# 3-5_TDR.net
KiCad netlist of a schematic drawn in Altium Designer
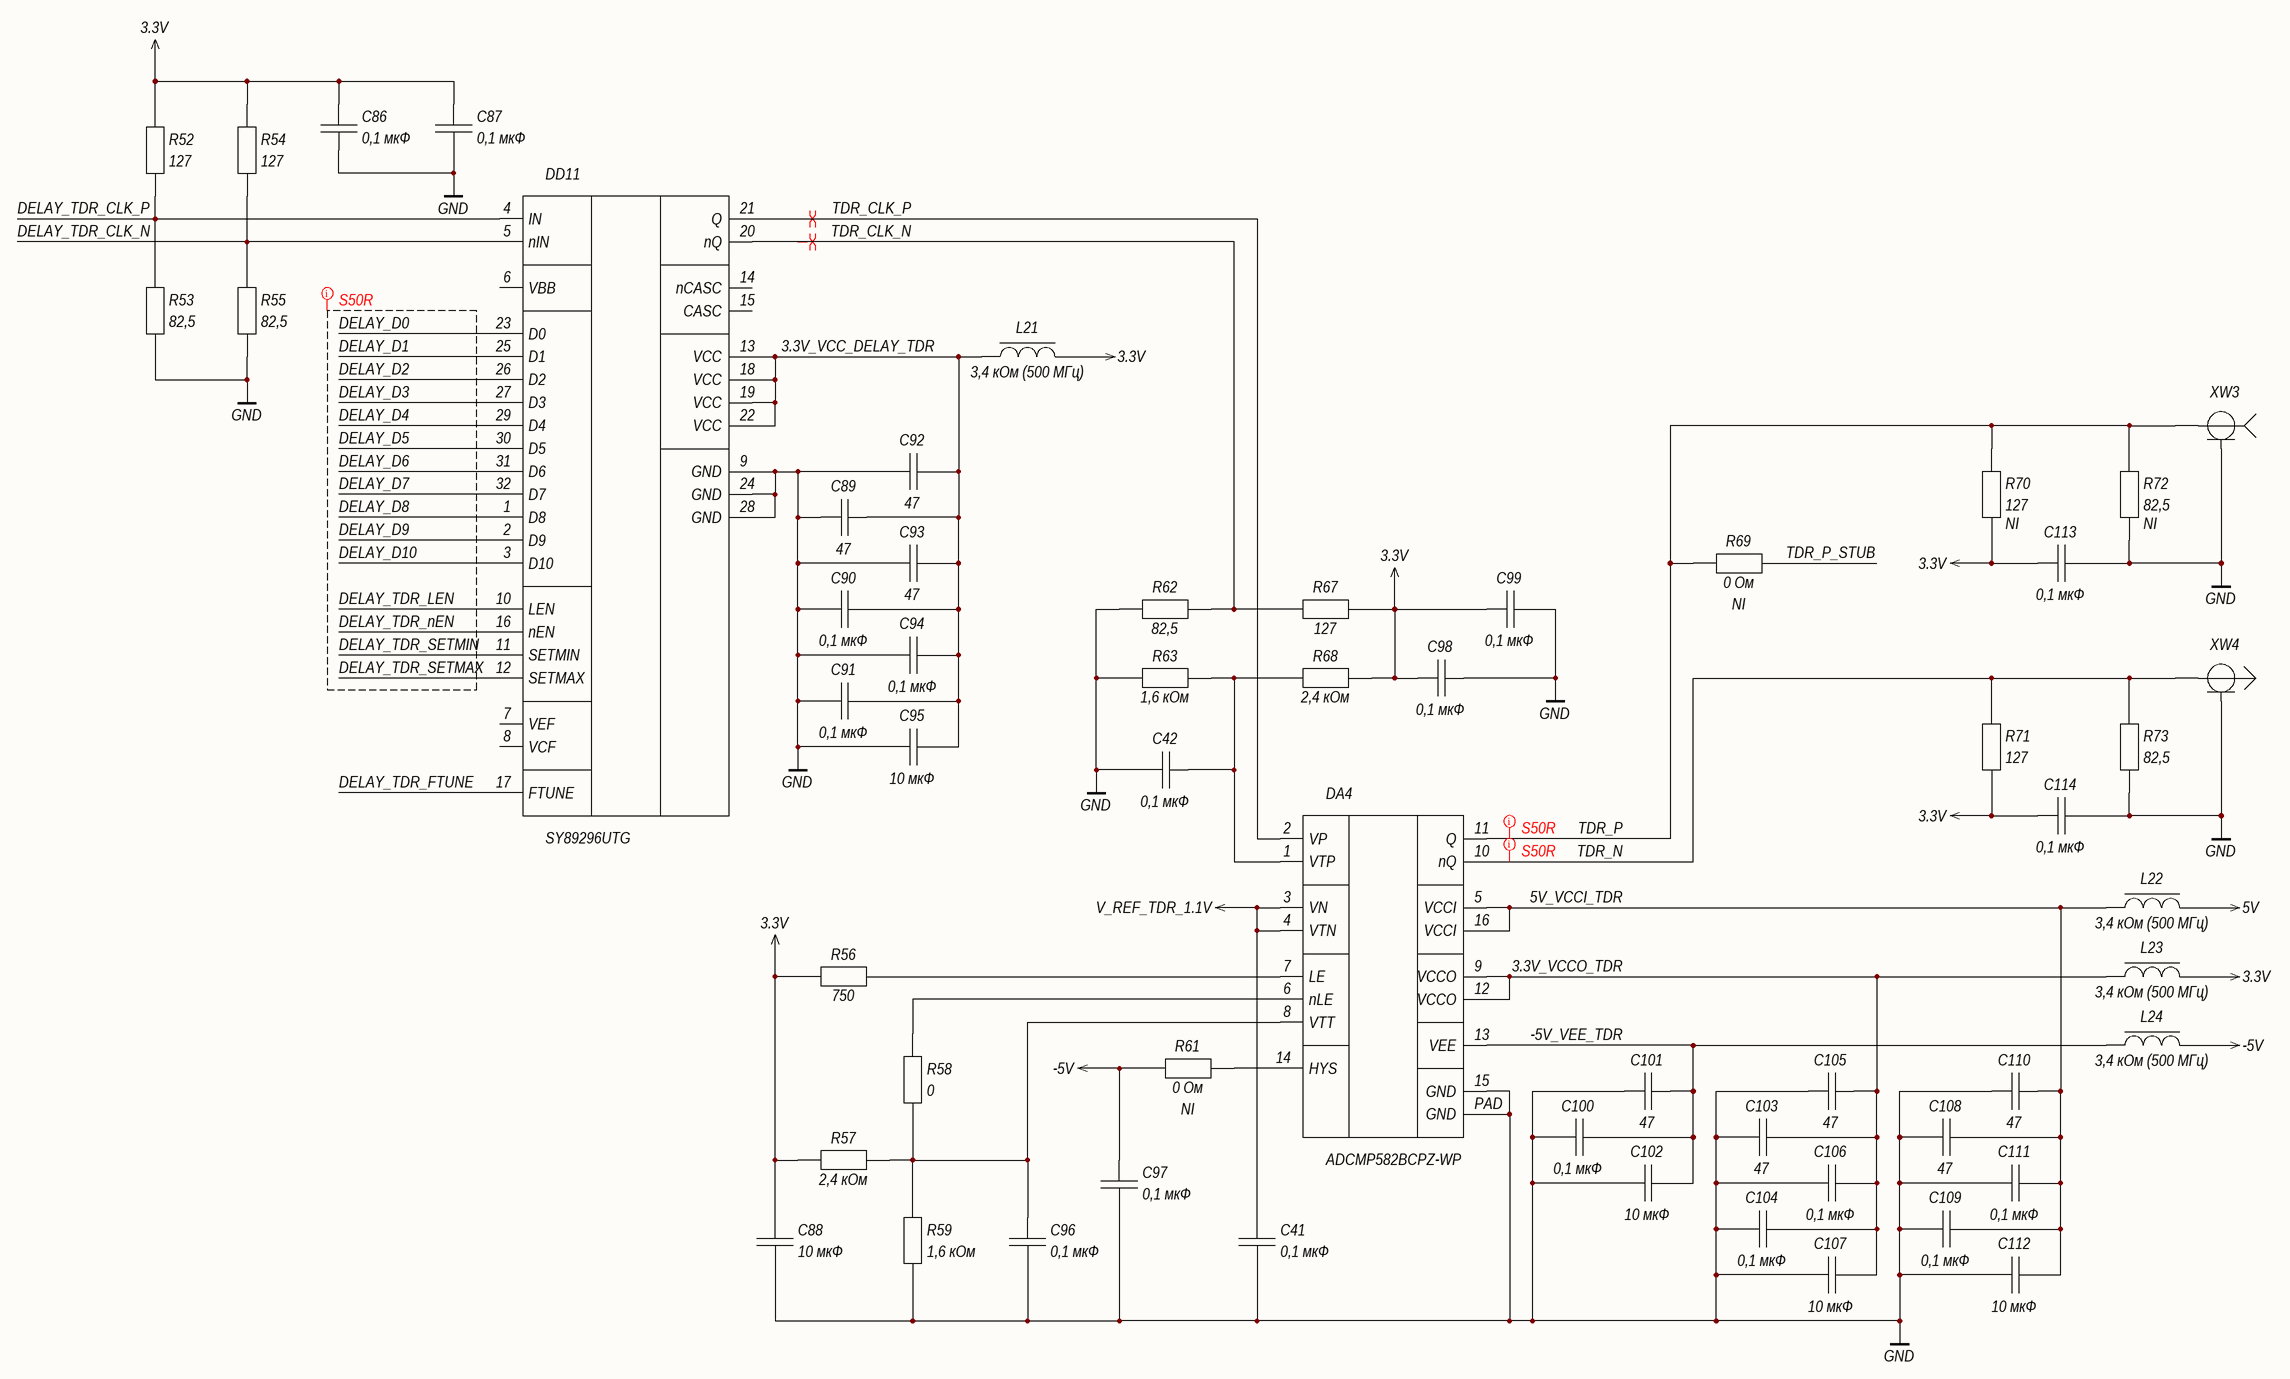
[diagram p0: Э3-5 TDR Генератор.SchDoc]

(export (version "E")
  (design (tool "Eeschema 10.0.6"))
  (components
    (comp (ref "C41")
      (value "0,1 мкФ")
      (footprint "C0402-B-0.5mm")
      (description "0402 X7R 0,1 мкФ ±10 % 50 В")
      (fields (field (name "PARTNUMBER") "GRM155R71H104KE14D"))
      (libsource (lib "Capacitors") (part "Non Polar Ver."))
    )
    (comp (ref "C42")
      (value "0,1 мкФ")
      (footprint "C0402-B-0.5mm")
      (description "0402 X7R 0,1 мкФ ±10 % 50 В")
      (fields (field (name "PARTNUMBER") "GRM155R71H104KE14D"))
      (libsource (lib "Capacitors") (part "Non Polar Hor."))
    )
    (comp (ref "C86")
      (value "0,1 мкФ")
      (footprint "C0402-B-0.5mm")
      (description "0402 X7R 0,1 мкФ ±10 % 50 В")
      (fields (field (name "PARTNUMBER") "GRM155R71H104KE14D"))
      (libsource (lib "Capacitors") (part "Non Polar Ver."))
    )
    (comp (ref "C87")
      (value "0,1 мкФ")
      (footprint "C0402-B-0.5mm")
      (description "0402 X7R 0,1 мкФ ±10 % 50 В")
      (fields (field (name "PARTNUMBER") "GRM155R71H104KE14D"))
      (libsource (lib "Capacitors") (part "Non Polar Ver."))
    )
    (comp (ref "C88")
      (value "10 мкФ")
      (footprint "C0603-B-0.8mm")
      (description "0603 X5R 10 мкФ ±20 % 25 В")
      (fields (field (name "PARTNUMBER") "GRM188R61E106MA73"))
      (libsource (lib "Capacitors") (part "Non Polar Ver."))
    )
    (comp (ref "C89")
      (value "47")
      (footprint "C0402-B-0.5mm")
      (description "0402 NP0 47 пФ ±5 % 50 В")
      (fields (field (name "PARTNUMBER") "GCM1555C1H470JA16"))
      (libsource (lib "Capacitors") (part "Non Polar Hor."))
    )
    (comp (ref "C90")
      (value "0,1 мкФ")
      (footprint "C0402-B-0.5mm")
      (description "0402 X7R 0,1 мкФ ±10 % 50 В")
      (fields (field (name "PARTNUMBER") "GRM155R71H104KE14D"))
      (libsource (lib "Capacitors") (part "Non Polar Hor."))
    )
    (comp (ref "C91")
      (value "0,1 мкФ")
      (footprint "C0402-B-0.5mm")
      (description "0402 X7R 0,1 мкФ ±10 % 50 В")
      (fields (field (name "PARTNUMBER") "GRM155R71H104KE14D"))
      (libsource (lib "Capacitors") (part "Non Polar Hor."))
    )
    (comp (ref "C92")
      (value "47")
      (footprint "C0402-B-0.5mm")
      (description "0402 NP0 47 пФ ±5 % 50 В")
      (fields (field (name "PARTNUMBER") "GCM1555C1H470JA16"))
      (libsource (lib "Capacitors") (part "Non Polar Hor."))
    )
    (comp (ref "C93")
      (value "47")
      (footprint "C0402-B-0.5mm")
      (description "0402 NP0 47 пФ ±5 % 50 В")
      (fields (field (name "PARTNUMBER") "GCM1555C1H470JA16"))
      (libsource (lib "Capacitors") (part "Non Polar Hor."))
    )
    (comp (ref "C94")
      (value "0,1 мкФ")
      (footprint "C0402-B-0.5mm")
      (description "0402 X7R 0,1 мкФ ±10 % 50 В")
      (fields (field (name "PARTNUMBER") "GRM155R71H104KE14D"))
      (libsource (lib "Capacitors") (part "Non Polar Hor."))
    )
    (comp (ref "C95")
      (value "10 мкФ")
      (footprint "C0603-B-0.8mm")
      (description "0603 X5R 10 мкФ ±20 % 25 В")
      (fields (field (name "PARTNUMBER") "GRM188R61E106MA73"))
      (libsource (lib "Capacitors") (part "Non Polar Hor."))
    )
    (comp (ref "C96")
      (value "0,1 мкФ")
      (footprint "C0402-B-0.5mm")
      (description "0402 X7R 0,1 мкФ ±10 % 50 В")
      (fields (field (name "PARTNUMBER") "GRM155R71H104KE14D"))
      (libsource (lib "Capacitors") (part "Non Polar Ver."))
    )
    (comp (ref "C97")
      (value "0,1 мкФ")
      (footprint "C0402-B-0.5mm")
      (description "0402 X7R 0,1 мкФ ±10 % 50 В")
      (fields (field (name "PARTNUMBER") "GRM155R71H104KE14D"))
      (libsource (lib "Capacitors") (part "Non Polar Ver."))
    )
    (comp (ref "C98")
      (value "0,1 мкФ")
      (footprint "C0402-B-0.5mm")
      (description "0402 X7R 0,1 мкФ ±10 % 50 В")
      (fields (field (name "PARTNUMBER") "GRM155R71H104KE14D"))
      (libsource (lib "Capacitors") (part "Non Polar Hor."))
    )
    (comp (ref "C99")
      (value "0,1 мкФ")
      (footprint "C0402-B-0.5mm")
      (description "0402 X7R 0,1 мкФ ±10 % 50 В")
      (fields (field (name "PARTNUMBER") "GRM155R71H104KE14D"))
      (libsource (lib "Capacitors") (part "Non Polar Hor."))
    )
    (comp (ref "C100")
      (value "0,1 мкФ")
      (footprint "C0402-B-0.5mm")
      (description "0402 X7R 0,1 мкФ ±10 % 50 В")
      (fields (field (name "PARTNUMBER") "GRM155R71H104KE14D"))
      (libsource (lib "Capacitors") (part "Non Polar Hor."))
    )
    (comp (ref "C101")
      (value "47")
      (footprint "C0402-B-0.5mm")
      (description "0402 NP0 47 пФ ±5 % 50 В")
      (fields (field (name "PARTNUMBER") "GCM1555C1H470JA16"))
      (libsource (lib "Capacitors") (part "Non Polar Hor."))
    )
    (comp (ref "C102")
      (value "10 мкФ")
      (footprint "C0603-B-0.8mm")
      (description "0603 X5R 10 мкФ ±20 % 25 В")
      (fields (field (name "PARTNUMBER") "GRM188R61E106MA73"))
      (libsource (lib "Capacitors") (part "Non Polar Hor."))
    )
    (comp (ref "C103")
      (value "47")
      (footprint "C0402-B-0.5mm")
      (description "0402 NP0 47 пФ ±5 % 50 В")
      (fields (field (name "PARTNUMBER") "GCM1555C1H470JA16"))
      (libsource (lib "Capacitors") (part "Non Polar Hor."))
    )
    (comp (ref "C104")
      (value "0,1 мкФ")
      (footprint "C0402-B-0.5mm")
      (description "0402 X7R 0,1 мкФ ±10 % 50 В")
      (fields (field (name "PARTNUMBER") "GRM155R71H104KE14D"))
      (libsource (lib "Capacitors") (part "Non Polar Hor."))
    )
    (comp (ref "C105")
      (value "47")
      (footprint "C0402-B-0.5mm")
      (description "0402 NP0 47 пФ ±5 % 50 В")
      (fields (field (name "PARTNUMBER") "GCM1555C1H470JA16"))
      (libsource (lib "Capacitors") (part "Non Polar Hor."))
    )
    (comp (ref "C106")
      (value "0,1 мкФ")
      (footprint "C0402-B-0.5mm")
      (description "0402 X7R 0,1 мкФ ±10 % 50 В")
      (fields (field (name "PARTNUMBER") "GRM155R71H104KE14D"))
      (libsource (lib "Capacitors") (part "Non Polar Hor."))
    )
    (comp (ref "C107")
      (value "10 мкФ")
      (footprint "C0603-B-0.8mm")
      (description "0603 X5R 10 мкФ ±20 % 25 В")
      (fields (field (name "PARTNUMBER") "GRM188R61E106MA73"))
      (libsource (lib "Capacitors") (part "Non Polar Hor."))
    )
    (comp (ref "C108")
      (value "47")
      (footprint "C0402-B-0.5mm")
      (description "0402 NP0 47 пФ ±5 % 50 В")
      (fields (field (name "PARTNUMBER") "GCM1555C1H470JA16"))
      (libsource (lib "Capacitors") (part "Non Polar Hor."))
    )
    (comp (ref "C109")
      (value "0,1 мкФ")
      (footprint "C0402-B-0.5mm")
      (description "0402 X7R 0,1 мкФ ±10 % 50 В")
      (fields (field (name "PARTNUMBER") "GRM155R71H104KE14D"))
      (libsource (lib "Capacitors") (part "Non Polar Hor."))
    )
    (comp (ref "C110")
      (value "47")
      (footprint "C0402-B-0.5mm")
      (description "0402 NP0 47 пФ ±5 % 50 В")
      (fields (field (name "PARTNUMBER") "GCM1555C1H470JA16"))
      (libsource (lib "Capacitors") (part "Non Polar Hor."))
    )
    (comp (ref "C111")
      (value "0,1 мкФ")
      (footprint "C0402-B-0.5mm")
      (description "0402 X7R 0,1 мкФ ±10 % 50 В")
      (fields (field (name "PARTNUMBER") "GRM155R71H104KE14D"))
      (libsource (lib "Capacitors") (part "Non Polar Hor."))
    )
    (comp (ref "C112")
      (value "10 мкФ")
      (footprint "C0603-B-0.8mm")
      (description "0603 X5R 10 мкФ ±20 % 25 В")
      (fields (field (name "PARTNUMBER") "GRM188R61E106MA73"))
      (libsource (lib "Capacitors") (part "Non Polar Hor."))
    )
    (comp (ref "C113")
      (value "0,1 мкФ")
      (footprint "C0402-B-0.5mm")
      (description "0402 X7R 0,1 мкФ ±10 % 50 В")
      (fields (field (name "PARTNUMBER") "GRM155R71H104KE14D"))
      (libsource (lib "Capacitors") (part "Non Polar Hor."))
    )
    (comp (ref "C114")
      (value "0,1 мкФ")
      (footprint "C0402-B-0.5mm")
      (description "0402 X7R 0,1 мкФ ±10 % 50 В")
      (fields (field (name "PARTNUMBER") "GRM155R71H104KE14D"))
      (libsource (lib "Capacitors") (part "Non Polar Hor."))
    )
    (comp (ref "DA4")
      (value "ADCMP582BCPZ-WP")
      (footprint "16-LFCSP-3-H0.75")
      (description "Ultrafast SiGe Voltage Comparators")
      (fields (field (name "MANUFACTURER") "Analog Devices, Inc."))
      (libsource (lib "Analog") (part "ADCMP582"))
    )
    (comp (ref "DD11")
      (value "SY89296UTG")
      (footprint "32-TQFP-B")
      (description "2.5V/3.3V, 1.5 GHz, LVPECL Programmable Delay with Fine Tune Control")
      (fields (field (name "MANUFACTURER") "Microchip"))
      (libsource (lib "Digital") (part "SY89296UTG"))
    )
    (comp (ref "L21")
      (value "3,4 кОм (500 МГц)")
      (footprint "L0402-B-0.5mm")
      (fields (field (name "PARTNUMBER") "BLM15HD182BH1"))
      (libsource (lib "Inductors") (part "Inductor MC Hor."))
    )
    (comp (ref "L22")
      (value "3,4 кОм (500 МГц)")
      (footprint "L0402-B-0.5mm")
      (fields (field (name "PARTNUMBER") "BLM15HD182BH1"))
      (libsource (lib "Inductors") (part "Inductor MC Hor."))
    )
    (comp (ref "L23")
      (value "3,4 кОм (500 МГц)")
      (footprint "L0402-B-0.5mm")
      (fields (field (name "PARTNUMBER") "BLM15HD182BH1"))
      (libsource (lib "Inductors") (part "Inductor MC Hor."))
    )
    (comp (ref "L24")
      (value "3,4 кОм (500 МГц)")
      (footprint "L0402-B-0.5mm")
      (fields (field (name "PARTNUMBER") "BLM15HD182BH1"))
      (libsource (lib "Inductors") (part "Inductor MC Hor."))
    )
    (comp (ref "R52")
      (value "127")
      (footprint "CR0402-B-0.35mm")
      (description "0402 127 Ом ±1 %")
      (libsource (lib "Resistors") (part "Resistor Ver."))
    )
    (comp (ref "R53")
      (value "82,5")
      (footprint "CR0402-B-0.35mm")
      (description "0402 82,5 Ом ±1 %")
      (libsource (lib "Resistors") (part "Resistor Ver."))
    )
    (comp (ref "R54")
      (value "127")
      (footprint "CR0402-B-0.35mm")
      (description "0402 127 Ом ±1 %")
      (libsource (lib "Resistors") (part "Resistor Ver."))
    )
    (comp (ref "R55")
      (value "82,5")
      (footprint "CR0402-B-0.35mm")
      (description "0402 82,5 Ом ±1 %")
      (libsource (lib "Resistors") (part "Resistor Ver."))
    )
    (comp (ref "R56")
      (value "750")
      (footprint "CR0402-B-0.35mm")
      (description "0402 750 Ом ±5 %")
      (libsource (lib "Resistors") (part "Resistor Hor."))
    )
    (comp (ref "R57")
      (value "2,4 кОм")
      (footprint "CR0402-B-0.35mm")
      (description "0402 2,4 кОм ±1 %")
      (libsource (lib "Resistors") (part "Resistor Hor."))
    )
    (comp (ref "R58")
      (value "0")
      (footprint "CR0402-B-0.35mm")
      (description "0402 0 Ом")
      (libsource (lib "Resistors") (part "Resistor Ver."))
    )
    (comp (ref "R59")
      (value "1,6 кОм")
      (footprint "CR0402-B-0.35mm")
      (description "0402 1,6 кОм ±1 %")
      (libsource (lib "Resistors") (part "Resistor Ver."))
    )
    (comp (ref "R61")
      (value "0 Ом")
      (footprint "CR0402-B-0.35mm")
      (description "0402 0 Ом")
      (fields (field (name "COMPONENTTYPE") "NI"))
      (libsource (lib "Resistors") (part "Resistor Hor."))
    )
    (comp (ref "R62")
      (value "82,5")
      (footprint "CR0402-B-0.35mm")
      (description "0402 82,5 Ом ±1 %")
      (libsource (lib "Resistors") (part "Resistor Hor."))
    )
    (comp (ref "R63")
      (value "1,6 кОм")
      (footprint "CR0402-B-0.35mm")
      (description "0402 1,6 кОм ±1 %")
      (libsource (lib "Resistors") (part "Resistor Hor."))
    )
    (comp (ref "R67")
      (value "127")
      (footprint "CR0402-B-0.35mm")
      (description "0402 127 Ом ±1 %")
      (libsource (lib "Resistors") (part "Resistor Hor."))
    )
    (comp (ref "R68")
      (value "2,4 кОм")
      (footprint "CR0402-B-0.35mm")
      (description "0402 2,4 кОм ±1 %")
      (libsource (lib "Resistors") (part "Resistor Hor."))
    )
    (comp (ref "R69")
      (value "0 Ом")
      (footprint "CR0402-B-0.35mm")
      (description "0402 0 Ом")
      (fields (field (name "COMPONENTTYPE") "NI"))
      (libsource (lib "Resistors") (part "Resistor Hor."))
    )
    (comp (ref "R70")
      (value "127")
      (footprint "CR0402-B-0.35mm")
      (description "0402 127 Ом ±1 %")
      (fields (field (name "COMPONENTTYPE") "NI"))
      (libsource (lib "Resistors") (part "Resistor Ver."))
    )
    (comp (ref "R71")
      (value "127")
      (footprint "CR0402-B-0.35mm")
      (description "0402 127 Ом ±1 %")
      (libsource (lib "Resistors") (part "Resistor Ver."))
    )
    (comp (ref "R72")
      (value "82,5")
      (footprint "CR0402-B-0.35mm")
      (description "0402 82,5 Ом ±1 %")
      (fields (field (name "COMPONENTTYPE") "NI"))
      (libsource (lib "Resistors") (part "Resistor Ver."))
    )
    (comp (ref "R73")
      (value "82,5")
      (footprint "CR0402-B-0.35mm")
      (description "0402 82,5 Ом ±1 %")
      (libsource (lib "Resistors") (part "Resistor Ver."))
    )
    (comp (ref "XW3")
      (value "XW(S)")
      (footprint "SMA-J-P-H-ST-EM1")
      (libsource (lib "Connectors") (part "XW(S)"))
    )
    (comp (ref "XW4")
      (value "XW(P)")
      (footprint "U.FL STR PLG")
      (libsource (lib "Connectors") (part "XW(P)"))
    )
  )
  (nets
    (net (code "1") (name "-5V") (class "Default")
      (node (ref "C97") (pin "1") (pinfunction "1_1") (pintype "passive"))
      (node (ref "L24") (pin "2") (pinfunction "2_2") (pintype "passive"))
      (node (ref "R61") (pin "1") (pinfunction "1_1") (pintype "passive"))
    )
    (net (code "2") (name "/-5V_VEE_TDR") (class "Default")
      (node (ref "C100") (pin "2") (pinfunction "2_2") (pintype "passive"))
      (node (ref "C101") (pin "2") (pinfunction "2_2") (pintype "passive"))
      (node (ref "C102") (pin "2") (pinfunction "2_2") (pintype "passive"))
      (node (ref "DA4") (pin "13") (pinfunction "VEE_13") (pintype "passive"))
      (node (ref "L24") (pin "1") (pinfunction "1_1") (pintype "passive"))
    )
    (net (code "3") (name "/3.3V_VCCO_TDR") (class "Default")
      (node (ref "C103") (pin "2") (pinfunction "2_2") (pintype "passive"))
      (node (ref "C104") (pin "2") (pinfunction "2_2") (pintype "passive"))
      (node (ref "C105") (pin "2") (pinfunction "2_2") (pintype "passive"))
      (node (ref "C106") (pin "2") (pinfunction "2_2") (pintype "passive"))
      (node (ref "C107") (pin "2") (pinfunction "2_2") (pintype "passive"))
      (node (ref "DA4") (pin "12") (pinfunction "VCCO_12") (pintype "passive"))
      (node (ref "DA4") (pin "9") (pinfunction "VCCO_9") (pintype "passive"))
      (node (ref "L23") (pin "1") (pinfunction "1_1") (pintype "passive"))
    )
    (net (code "4") (name "/3.3V_VCC_DELAY_TDR") (class "Default")
      (node (ref "C89") (pin "2") (pinfunction "2_2") (pintype "passive"))
      (node (ref "C90") (pin "2") (pinfunction "2_2") (pintype "passive"))
      (node (ref "C91") (pin "2") (pinfunction "2_2") (pintype "passive"))
      (node (ref "C92") (pin "2") (pinfunction "2_2") (pintype "passive"))
      (node (ref "C93") (pin "2") (pinfunction "2_2") (pintype "passive"))
      (node (ref "C94") (pin "2") (pinfunction "2_2") (pintype "passive"))
      (node (ref "C95") (pin "2") (pinfunction "2_2") (pintype "passive"))
      (node (ref "DD11") (pin "13") (pinfunction "VCC_13") (pintype "passive"))
      (node (ref "DD11") (pin "18") (pinfunction "VCC_18") (pintype "passive"))
      (node (ref "DD11") (pin "19") (pinfunction "VCC_19") (pintype "passive"))
      (node (ref "DD11") (pin "22") (pinfunction "VCC_22") (pintype "passive"))
      (node (ref "L21") (pin "1") (pinfunction "1_1") (pintype "passive"))
    )
    (net (code "5") (name "/5V_VCCI_TDR") (class "Default")
      (node (ref "C108") (pin "2") (pinfunction "2_2") (pintype "passive"))
      (node (ref "C109") (pin "2") (pinfunction "2_2") (pintype "passive"))
      (node (ref "C110") (pin "2") (pinfunction "2_2") (pintype "passive"))
      (node (ref "C111") (pin "2") (pinfunction "2_2") (pintype "passive"))
      (node (ref "C112") (pin "2") (pinfunction "2_2") (pintype "passive"))
      (node (ref "DA4") (pin "16") (pinfunction "VCCI_16") (pintype "passive"))
      (node (ref "DA4") (pin "5") (pinfunction "VCCI_5") (pintype "passive"))
      (node (ref "L22") (pin "1") (pinfunction "1_1") (pintype "passive"))
    )
    (net (code "6") (name "/DELAY_D0") (class "Default")
      (node (ref "DD11") (pin "23") (pinfunction "D0_23") (pintype "passive"))
    )
    (net (code "7") (name "/DELAY_D1") (class "Default")
      (node (ref "DD11") (pin "25") (pinfunction "D1_25") (pintype "passive"))
    )
    (net (code "8") (name "/DELAY_D2") (class "Default")
      (node (ref "DD11") (pin "26") (pinfunction "D2_26") (pintype "passive"))
    )
    (net (code "9") (name "/DELAY_D3") (class "Default")
      (node (ref "DD11") (pin "27") (pinfunction "D3_27") (pintype "passive"))
    )
    (net (code "10") (name "/DELAY_D4") (class "Default")
      (node (ref "DD11") (pin "29") (pinfunction "D4_29") (pintype "passive"))
    )
    (net (code "11") (name "/DELAY_D5") (class "Default")
      (node (ref "DD11") (pin "30") (pinfunction "D5_30") (pintype "passive"))
    )
    (net (code "12") (name "/DELAY_D6") (class "Default")
      (node (ref "DD11") (pin "31") (pinfunction "D6_31") (pintype "passive"))
    )
    (net (code "13") (name "/DELAY_D7") (class "Default")
      (node (ref "DD11") (pin "32") (pinfunction "D7_32") (pintype "passive"))
    )
    (net (code "14") (name "/DELAY_D8") (class "Default")
      (node (ref "DD11") (pin "1") (pinfunction "D8_1") (pintype "passive"))
    )
    (net (code "15") (name "/DELAY_D9") (class "Default")
      (node (ref "DD11") (pin "2") (pinfunction "D9_2") (pintype "passive"))
    )
    (net (code "16") (name "/DELAY_D10") (class "Default")
      (node (ref "DD11") (pin "3") (pinfunction "D10_3") (pintype "passive"))
    )
    (net (code "17") (name "/DELAY_TDR_CLK_N") (class "Default")
      (node (ref "DD11") (pin "5") (pinfunction "nIN_5") (pintype "passive"))
      (node (ref "R54") (pin "2") (pinfunction "2_2") (pintype "passive"))
      (node (ref "R55") (pin "1") (pinfunction "1_1") (pintype "passive"))
    )
    (net (code "18") (name "/DELAY_TDR_CLK_P") (class "Default")
      (node (ref "DD11") (pin "4") (pinfunction "IN_4") (pintype "passive"))
      (node (ref "R52") (pin "2") (pinfunction "2_2") (pintype "passive"))
      (node (ref "R53") (pin "1") (pinfunction "1_1") (pintype "passive"))
    )
    (net (code "19") (name "/DELAY_TDR_FTUNE") (class "Default")
      (node (ref "DD11") (pin "17") (pinfunction "FTUNE_17") (pintype "passive"))
    )
    (net (code "20") (name "/DELAY_TDR_LEN") (class "Default")
      (node (ref "DD11") (pin "10") (pinfunction "LEN_10") (pintype "passive"))
    )
    (net (code "21") (name "/DELAY_TDR_SETMAX") (class "Default")
      (node (ref "DD11") (pin "12") (pinfunction "SETMAX_12") (pintype "passive"))
    )
    (net (code "22") (name "/DELAY_TDR_SETMIN") (class "Default")
      (node (ref "DD11") (pin "11") (pinfunction "SETMIN_11") (pintype "passive"))
    )
    (net (code "23") (name "/DELAY_TDR_nEN") (class "Default")
      (node (ref "DD11") (pin "16") (pinfunction "nEN_16") (pintype "passive"))
    )
    (net (code "24") (name "/TDR_CLK_N") (class "Default")
      (node (ref "DD11") (pin "20") (pinfunction "nQ_20") (pintype "passive"))
      (node (ref "R62") (pin "2") (pinfunction "2_2") (pintype "passive"))
      (node (ref "R67") (pin "1") (pinfunction "1_1") (pintype "passive"))
    )
    (net (code "25") (name "/TDR_CLK_P") (class "Default")
      (node (ref "DA4") (pin "2") (pinfunction "VP_2") (pintype "passive"))
      (node (ref "DD11") (pin "21") (pinfunction "Q_21") (pintype "passive"))
    )
    (net (code "26") (name "/TDR_N") (class "Default")
      (node (ref "DA4") (pin "10") (pinfunction "nQ_10") (pintype "passive"))
      (node (ref "R71") (pin "1") (pinfunction "1_1") (pintype "passive"))
      (node (ref "R73") (pin "1") (pinfunction "1_1") (pintype "passive"))
      (node (ref "XW4") (pin "1") (pinfunction "1_1") (pintype "passive"))
    )
    (net (code "27") (name "/TDR_P") (class "Default")
      (node (ref "DA4") (pin "11") (pinfunction "Q_11") (pintype "passive"))
      (node (ref "R69") (pin "1") (pinfunction "1_1") (pintype "passive"))
      (node (ref "R70") (pin "1") (pinfunction "1_1") (pintype "passive"))
      (node (ref "R72") (pin "1") (pinfunction "1_1") (pintype "passive"))
      (node (ref "XW3") (pin "1") (pinfunction "1_1") (pintype "passive"))
    )
    (net (code "28") (name "/TDR_P_STUB") (class "Default")
      (node (ref "R69") (pin "2") (pinfunction "2_2") (pintype "passive"))
    )
    (net (code "29") (name "3.3V") (class "Default")
      (node (ref "C113") (pin "1") (pinfunction "1_1") (pintype "passive"))
      (node (ref "C114") (pin "1") (pinfunction "1_1") (pintype "passive"))
      (node (ref "C86") (pin "1") (pinfunction "1_1") (pintype "passive"))
      (node (ref "C87") (pin "1") (pinfunction "1_1") (pintype "passive"))
      (node (ref "C88") (pin "1") (pinfunction "1_1") (pintype "passive"))
      (node (ref "C98") (pin "1") (pinfunction "1_1") (pintype "passive"))
      (node (ref "C99") (pin "1") (pinfunction "1_1") (pintype "passive"))
      (node (ref "L21") (pin "2") (pinfunction "2_2") (pintype "passive"))
      (node (ref "L23") (pin "2") (pinfunction "2_2") (pintype "passive"))
      (node (ref "R52") (pin "1") (pinfunction "1_1") (pintype "passive"))
      (node (ref "R54") (pin "1") (pinfunction "1_1") (pintype "passive"))
      (node (ref "R56") (pin "1") (pinfunction "1_1") (pintype "passive"))
      (node (ref "R57") (pin "1") (pinfunction "1_1") (pintype "passive"))
      (node (ref "R67") (pin "2") (pinfunction "2_2") (pintype "passive"))
      (node (ref "R68") (pin "2") (pinfunction "2_2") (pintype "passive"))
      (node (ref "R70") (pin "2") (pinfunction "2_2") (pintype "passive"))
      (node (ref "R71") (pin "2") (pinfunction "2_2") (pintype "passive"))
    )
    (net (code "30") (name "5V") (class "Default")
      (node (ref "L22") (pin "2") (pinfunction "2_2") (pintype "passive"))
    )
    (net (code "31") (name "GND") (class "Default")
      (node (ref "C100") (pin "1") (pinfunction "1_1") (pintype "passive"))
      (node (ref "C101") (pin "1") (pinfunction "1_1") (pintype "passive"))
      (node (ref "C102") (pin "1") (pinfunction "1_1") (pintype "passive"))
      (node (ref "C103") (pin "1") (pinfunction "1_1") (pintype "passive"))
      (node (ref "C104") (pin "1") (pinfunction "1_1") (pintype "passive"))
      (node (ref "C105") (pin "1") (pinfunction "1_1") (pintype "passive"))
      (node (ref "C106") (pin "1") (pinfunction "1_1") (pintype "passive"))
      (node (ref "C107") (pin "1") (pinfunction "1_1") (pintype "passive"))
      (node (ref "C108") (pin "1") (pinfunction "1_1") (pintype "passive"))
      (node (ref "C109") (pin "1") (pinfunction "1_1") (pintype "passive"))
      (node (ref "C110") (pin "1") (pinfunction "1_1") (pintype "passive"))
      (node (ref "C111") (pin "1") (pinfunction "1_1") (pintype "passive"))
      (node (ref "C112") (pin "1") (pinfunction "1_1") (pintype "passive"))
      (node (ref "C113") (pin "2") (pinfunction "2_2") (pintype "passive"))
      (node (ref "C114") (pin "2") (pinfunction "2_2") (pintype "passive"))
      (node (ref "C41") (pin "2") (pinfunction "2_2") (pintype "passive"))
      (node (ref "C42") (pin "1") (pinfunction "1_1") (pintype "passive"))
      (node (ref "C86") (pin "2") (pinfunction "2_2") (pintype "passive"))
      (node (ref "C87") (pin "2") (pinfunction "2_2") (pintype "passive"))
      (node (ref "C88") (pin "2") (pinfunction "2_2") (pintype "passive"))
      (node (ref "C89") (pin "1") (pinfunction "1_1") (pintype "passive"))
      (node (ref "C90") (pin "1") (pinfunction "1_1") (pintype "passive"))
      (node (ref "C91") (pin "1") (pinfunction "1_1") (pintype "passive"))
      (node (ref "C92") (pin "1") (pinfunction "1_1") (pintype "passive"))
      (node (ref "C93") (pin "1") (pinfunction "1_1") (pintype "passive"))
      (node (ref "C94") (pin "1") (pinfunction "1_1") (pintype "passive"))
      (node (ref "C95") (pin "1") (pinfunction "1_1") (pintype "passive"))
      (node (ref "C96") (pin "2") (pinfunction "2_2") (pintype "passive"))
      (node (ref "C97") (pin "2") (pinfunction "2_2") (pintype "passive"))
      (node (ref "C98") (pin "2") (pinfunction "2_2") (pintype "passive"))
      (node (ref "C99") (pin "2") (pinfunction "2_2") (pintype "passive"))
      (node (ref "DA4") (pin "15") (pinfunction "GND_15") (pintype "passive"))
      (node (ref "DA4") (pin "PAD") (pinfunction "GND_PAD") (pintype "passive"))
      (node (ref "DD11") (pin "24") (pinfunction "GND_24") (pintype "passive"))
      (node (ref "DD11") (pin "28") (pinfunction "GND_28") (pintype "passive"))
      (node (ref "DD11") (pin "9") (pinfunction "GND_9") (pintype "passive"))
      (node (ref "R53") (pin "2") (pinfunction "2_2") (pintype "passive"))
      (node (ref "R55") (pin "2") (pinfunction "2_2") (pintype "passive"))
      (node (ref "R59") (pin "2") (pinfunction "2_2") (pintype "passive"))
      (node (ref "R62") (pin "1") (pinfunction "1_1") (pintype "passive"))
      (node (ref "R63") (pin "1") (pinfunction "1_1") (pintype "passive"))
      (node (ref "R72") (pin "2") (pinfunction "2_2") (pintype "passive"))
      (node (ref "R73") (pin "2") (pinfunction "2_2") (pintype "passive"))
      (node (ref "XW3") (pin "2") (pinfunction "2_2") (pintype "passive"))
      (node (ref "XW4") (pin "2") (pinfunction "2_2") (pintype "passive"))
    )
    (net (code "32") (name "Net-(DA4-HYS)") (class "Default")
      (node (ref "DA4") (pin "14") (pinfunction "HYS_14") (pintype "passive"))
      (node (ref "R61") (pin "2") (pinfunction "2_2") (pintype "passive"))
    )
    (net (code "33") (name "Net-(DA4-LE)") (class "Default")
      (node (ref "DA4") (pin "7") (pinfunction "LE_7") (pintype "passive"))
      (node (ref "R56") (pin "2") (pinfunction "2_2") (pintype "passive"))
    )
    (net (code "34") (name "Net-(DA4-VTP)") (class "Default")
      (node (ref "C42") (pin "2") (pinfunction "2_2") (pintype "passive"))
      (node (ref "DA4") (pin "1") (pinfunction "VTP_1") (pintype "passive"))
      (node (ref "R63") (pin "2") (pinfunction "2_2") (pintype "passive"))
      (node (ref "R68") (pin "1") (pinfunction "1_1") (pintype "passive"))
    )
    (net (code "35") (name "Net-(DA4-VTT)") (class "Default")
      (node (ref "C96") (pin "1") (pinfunction "1_1") (pintype "passive"))
      (node (ref "DA4") (pin "8") (pinfunction "VTT_8") (pintype "passive"))
      (node (ref "R57") (pin "2") (pinfunction "2_2") (pintype "passive"))
      (node (ref "R58") (pin "2") (pinfunction "2_2") (pintype "passive"))
      (node (ref "R59") (pin "1") (pinfunction "1_1") (pintype "passive"))
    )
    (net (code "36") (name "Net-(DA4-nLE)") (class "Default")
      (node (ref "DA4") (pin "6") (pinfunction "nLE_6") (pintype "passive"))
      (node (ref "R58") (pin "1") (pinfunction "1_1") (pintype "passive"))
    )
    (net (code "37") (name "V_REF_TDR_1.1V") (class "Default")
      (node (ref "C41") (pin "1") (pinfunction "1_1") (pintype "passive"))
      (node (ref "DA4") (pin "3") (pinfunction "VN_3") (pintype "passive"))
      (node (ref "DA4") (pin "4") (pinfunction "VTN_4") (pintype "passive"))
    )
    (net (code "38") (name "unconnected-(DD11-CASC-Pad15)") (class "Default")
      (node (ref "DD11") (pin "15") (pinfunction "CASC_15") (pintype "passive"))
    )
    (net (code "39") (name "unconnected-(DD11-VBB-Pad6)") (class "Default")
      (node (ref "DD11") (pin "6") (pinfunction "VBB_6") (pintype "passive"))
    )
    (net (code "40") (name "unconnected-(DD11-VCF-Pad8)") (class "Default")
      (node (ref "DD11") (pin "8") (pinfunction "VCF_8") (pintype "passive"))
    )
    (net (code "41") (name "unconnected-(DD11-VEF-Pad7)") (class "Default")
      (node (ref "DD11") (pin "7") (pinfunction "VEF_7") (pintype "passive"))
    )
    (net (code "42") (name "unconnected-(DD11-nCASC-Pad14)") (class "Default")
      (node (ref "DD11") (pin "14") (pinfunction "nCASC_14") (pintype "passive"))
    )
  )
)
